# vl822.net
KiCad netlist of a schematic drawn in Altium Designer
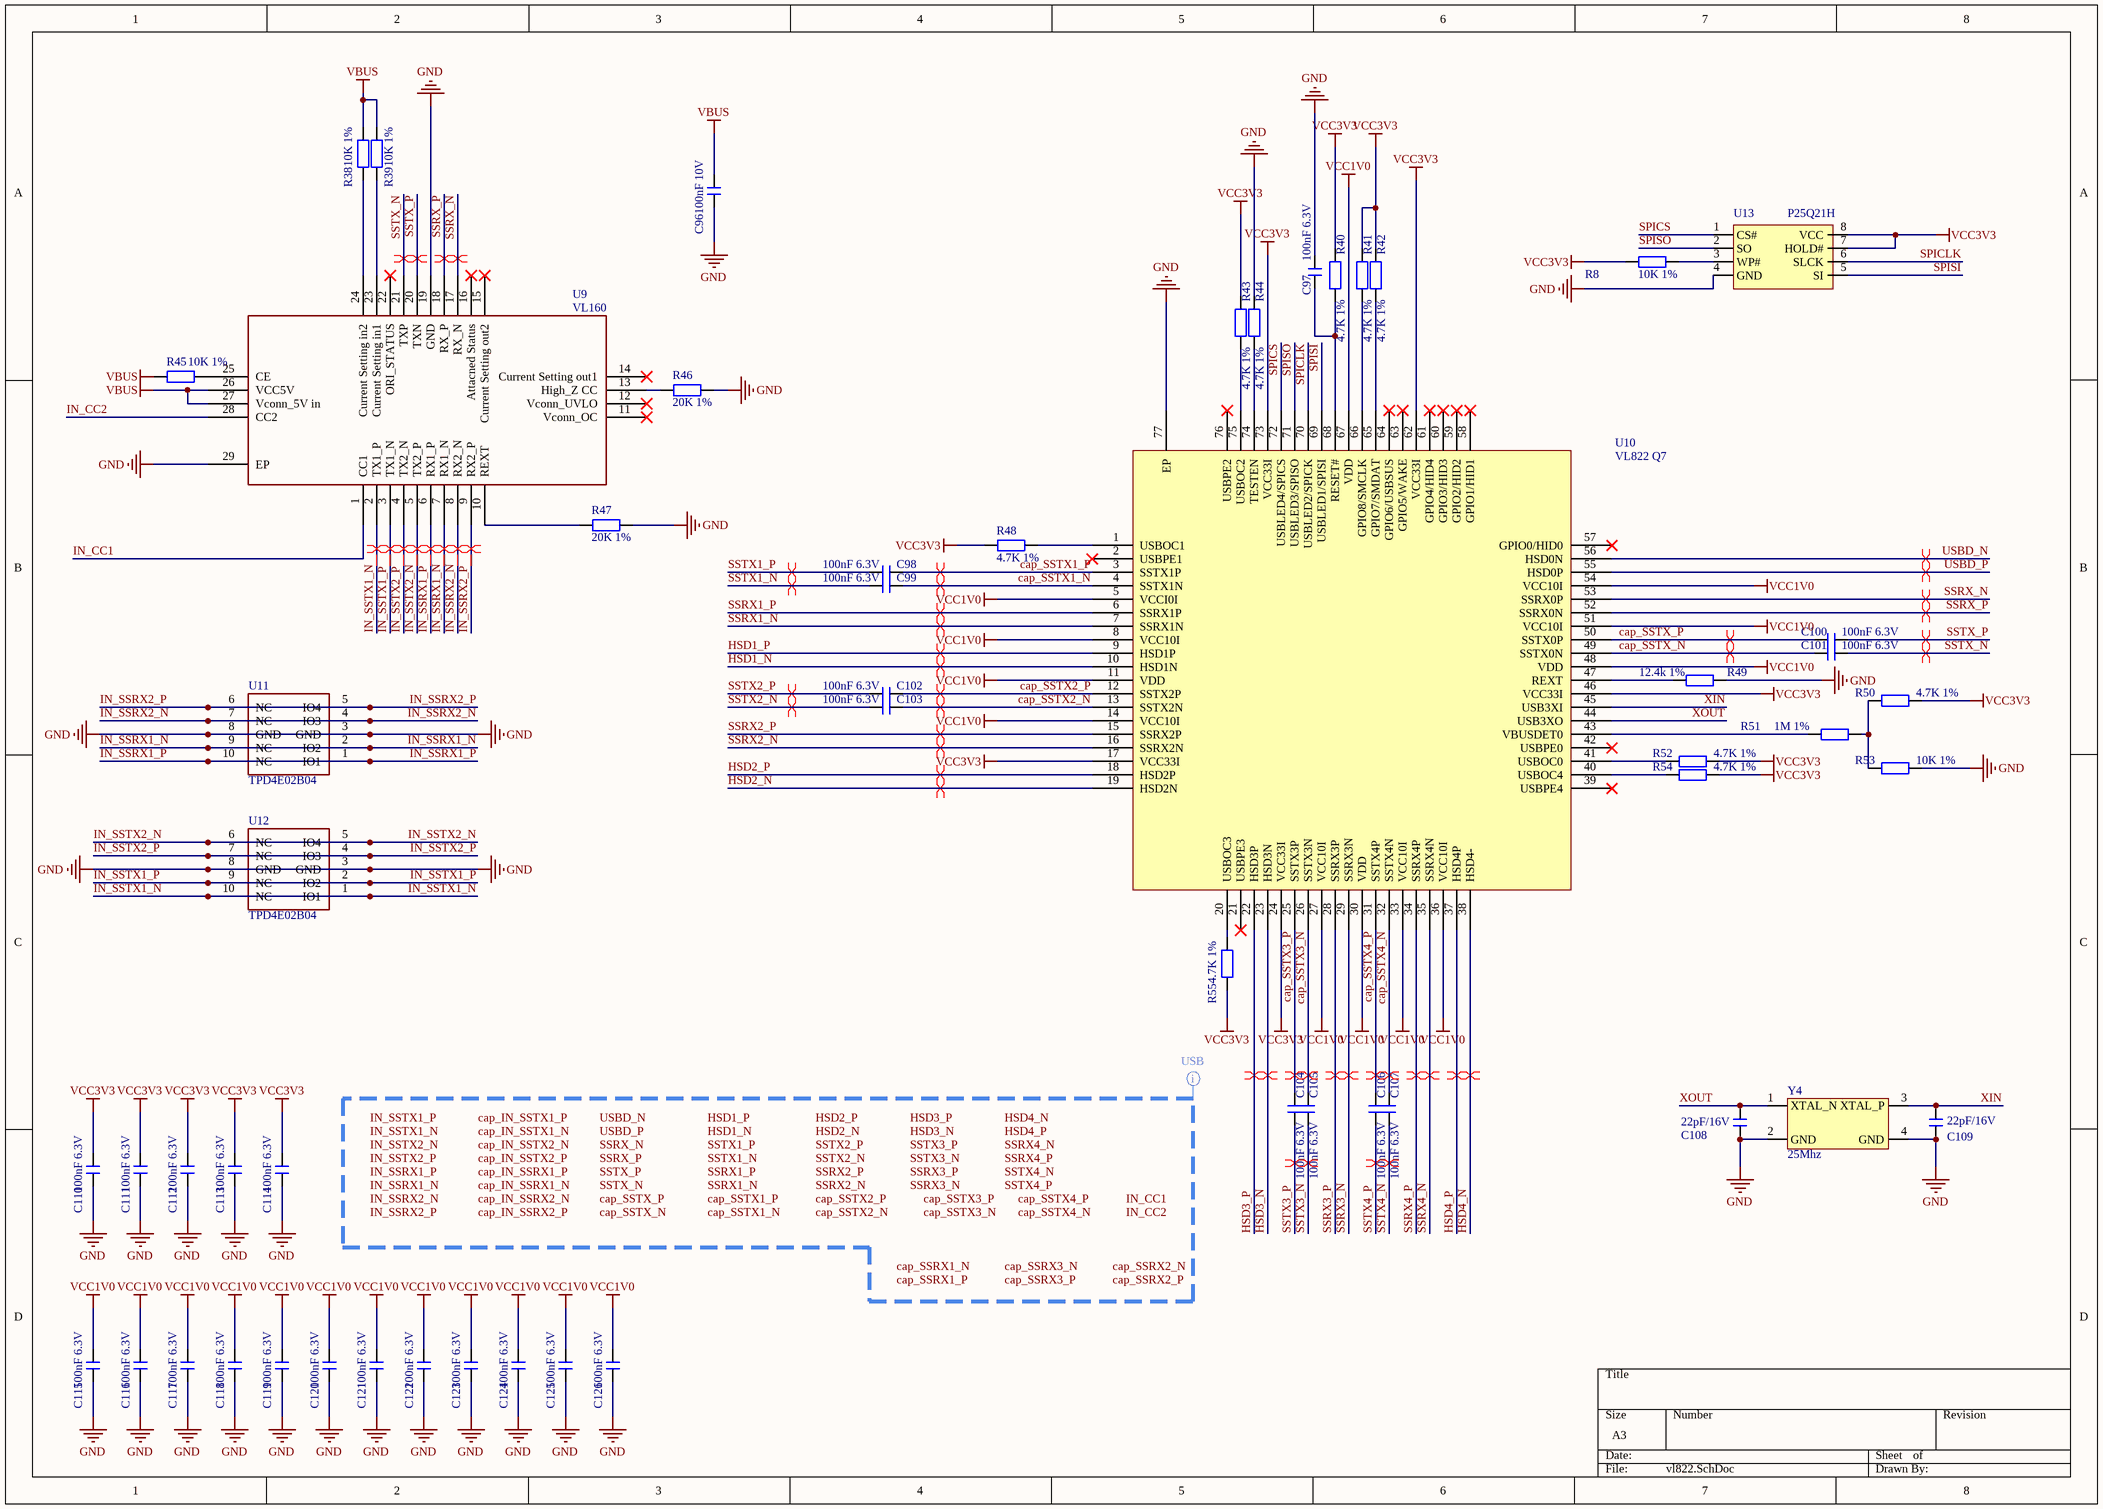
[diagram p0: vl822.SchDoc]

(export (version "E")
  (design (tool "Eeschema 10.0.6"))
  (components
    (comp (ref "C96")
      (value "100nF 10V")
      (footprint "C0402_L")
      (description "无极性贴片电容")
      (fields (field (name "版权归属") "源创客"))
      (libsource (lib "Capacitor") (part "C"))
    )
    (comp (ref "C97")
      (value "100nF 6.3V")
      (footprint "C0402_L")
      (description "无极性贴片电容")
      (fields (field (name "版权归属") "源创客"))
      (libsource (lib "Capacitor") (part "C"))
    )
    (comp (ref "C98")
      (value "100nF 6.3V")
      (footprint "C0402_L")
      (description "无极性贴片电容")
      (fields (field (name "版权归属") "源创客"))
      (libsource (lib "Capacitor") (part "C"))
    )
    (comp (ref "C99")
      (value "100nF 6.3V")
      (footprint "C0402_L")
      (description "无极性贴片电容")
      (fields (field (name "版权归属") "源创客"))
      (libsource (lib "Capacitor") (part "C"))
    )
    (comp (ref "C100")
      (value "100nF 6.3V")
      (footprint "C0402_L")
      (description "无极性贴片电容")
      (fields (field (name "版权归属") "源创客"))
      (libsource (lib "Capacitor") (part "C"))
    )
    (comp (ref "C101")
      (value "100nF 6.3V")
      (footprint "C0402_L")
      (description "无极性贴片电容")
      (fields (field (name "版权归属") "源创客"))
      (libsource (lib "Capacitor") (part "C"))
    )
    (comp (ref "C102")
      (value "100nF 6.3V")
      (footprint "C0402_L")
      (description "无极性贴片电容")
      (fields (field (name "版权归属") "源创客"))
      (libsource (lib "Capacitor") (part "C"))
    )
    (comp (ref "C103")
      (value "100nF 6.3V")
      (footprint "C0402_L")
      (description "无极性贴片电容")
      (fields (field (name "版权归属") "源创客"))
      (libsource (lib "Capacitor") (part "C"))
    )
    (comp (ref "C104")
      (value "100nF 6.3V")
      (footprint "C0402_L")
      (description "无极性贴片电容")
      (fields (field (name "版权归属") "源创客"))
      (libsource (lib "Capacitor") (part "C"))
    )
    (comp (ref "C105")
      (value "100nF 6.3V")
      (footprint "C0402_L")
      (description "无极性贴片电容")
      (fields (field (name "版权归属") "源创客"))
      (libsource (lib "Capacitor") (part "C"))
    )
    (comp (ref "C106")
      (value "100nF 6.3V")
      (footprint "C0402_L")
      (description "无极性贴片电容")
      (fields (field (name "版权归属") "源创客"))
      (libsource (lib "Capacitor") (part "C"))
    )
    (comp (ref "C107")
      (value "100nF 6.3V")
      (footprint "C0402_L")
      (description "无极性贴片电容")
      (fields (field (name "版权归属") "源创客"))
      (libsource (lib "Capacitor") (part "C"))
    )
    (comp (ref "C108")
      (value "22pF/16V")
      (footprint "C0402_L")
      (description "无极性贴片电容")
      (fields (field (name "版权归属") "源创客"))
      (libsource (lib "Capacitor") (part "C"))
    )
    (comp (ref "C109")
      (value "22pF/16V")
      (footprint "C0402_L")
      (description "无极性贴片电容")
      (fields (field (name "版权归属") "源创客"))
      (libsource (lib "Capacitor") (part "C"))
    )
    (comp (ref "C110")
      (value "100nF 6.3V")
      (footprint "C0402_L")
      (description "无极性贴片电容")
      (fields (field (name "版权归属") "源创客"))
      (libsource (lib "Capacitor") (part "C"))
    )
    (comp (ref "C111")
      (value "100nF 6.3V")
      (footprint "C0402_L")
      (description "无极性贴片电容")
      (fields (field (name "版权归属") "源创客"))
      (libsource (lib "Capacitor") (part "C"))
    )
    (comp (ref "C112")
      (value "100nF 6.3V")
      (footprint "C0402_L")
      (description "无极性贴片电容")
      (fields (field (name "版权归属") "源创客"))
      (libsource (lib "Capacitor") (part "C"))
    )
    (comp (ref "C113")
      (value "100nF 6.3V")
      (footprint "C0402_L")
      (description "无极性贴片电容")
      (fields (field (name "版权归属") "源创客"))
      (libsource (lib "Capacitor") (part "C"))
    )
    (comp (ref "C114")
      (value "100nF 6.3V")
      (footprint "C0402_L")
      (description "无极性贴片电容")
      (fields (field (name "版权归属") "源创客"))
      (libsource (lib "Capacitor") (part "C"))
    )
    (comp (ref "C115")
      (value "100nF 6.3V")
      (footprint "C0402_L")
      (description "无极性贴片电容")
      (fields (field (name "版权归属") "源创客"))
      (libsource (lib "Capacitor") (part "C"))
    )
    (comp (ref "C116")
      (value "100nF 6.3V")
      (footprint "C0402_L")
      (description "无极性贴片电容")
      (fields (field (name "版权归属") "源创客"))
      (libsource (lib "Capacitor") (part "C"))
    )
    (comp (ref "C117")
      (value "100nF 6.3V")
      (footprint "C0402_L")
      (description "无极性贴片电容")
      (fields (field (name "版权归属") "源创客"))
      (libsource (lib "Capacitor") (part "C"))
    )
    (comp (ref "C118")
      (value "100nF 6.3V")
      (footprint "C0402_L")
      (description "无极性贴片电容")
      (fields (field (name "版权归属") "源创客"))
      (libsource (lib "Capacitor") (part "C"))
    )
    (comp (ref "C119")
      (value "100nF 6.3V")
      (footprint "C0402_L")
      (description "无极性贴片电容")
      (fields (field (name "版权归属") "源创客"))
      (libsource (lib "Capacitor") (part "C"))
    )
    (comp (ref "C120")
      (value "100nF 6.3V")
      (footprint "C0402_L")
      (description "无极性贴片电容")
      (fields (field (name "版权归属") "源创客"))
      (libsource (lib "Capacitor") (part "C"))
    )
    (comp (ref "C121")
      (value "100nF 6.3V")
      (footprint "C0402_L")
      (description "无极性贴片电容")
      (fields (field (name "版权归属") "源创客"))
      (libsource (lib "Capacitor") (part "C"))
    )
    (comp (ref "C122")
      (value "100nF 6.3V")
      (footprint "C0402_L")
      (description "无极性贴片电容")
      (fields (field (name "版权归属") "源创客"))
      (libsource (lib "Capacitor") (part "C"))
    )
    (comp (ref "C123")
      (value "100nF 6.3V")
      (footprint "C0402_L")
      (description "无极性贴片电容")
      (fields (field (name "版权归属") "源创客"))
      (libsource (lib "Capacitor") (part "C"))
    )
    (comp (ref "C124")
      (value "100nF 6.3V")
      (footprint "C0402_L")
      (description "无极性贴片电容")
      (fields (field (name "版权归属") "源创客"))
      (libsource (lib "Capacitor") (part "C"))
    )
    (comp (ref "C125")
      (value "100nF 6.3V")
      (footprint "C0402_L")
      (description "无极性贴片电容")
      (fields (field (name "版权归属") "源创客"))
      (libsource (lib "Capacitor") (part "C"))
    )
    (comp (ref "C126")
      (value "100nF 6.3V")
      (footprint "C0402_L")
      (description "无极性贴片电容")
      (fields (field (name "版权归属") "源创客"))
      (libsource (lib "Capacitor") (part "C"))
    )
    (comp (ref "R8")
      (value "10K 1%")
      (footprint "R0402_L")
      (description "贴片电阻")
      (fields (field (name "版权归属") "源创客"))
      (libsource (lib "Resistor") (part "R"))
    )
    (comp (ref "R38")
      (value "10K 1%")
      (footprint "R0402_L")
      (description "贴片电阻")
      (fields (field (name "版权归属") "源创客"))
      (libsource (lib "Resistor") (part "R"))
    )
    (comp (ref "R39")
      (value "10K 1%")
      (footprint "R0402_L")
      (description "贴片电阻")
      (fields (field (name "版权归属") "源创客"))
      (libsource (lib "Resistor") (part "R"))
    )
    (comp (ref "R40")
      (value "4.7K 1%")
      (footprint "R0402_L")
      (description "贴片电阻")
      (fields (field (name "版权归属") "源创客"))
      (libsource (lib "Resistor") (part "R"))
    )
    (comp (ref "R41")
      (value "4.7K 1%")
      (footprint "R0402_L")
      (description "贴片电阻")
      (fields (field (name "版权归属") "源创客"))
      (libsource (lib "Resistor") (part "R"))
    )
    (comp (ref "R42")
      (value "4.7K 1%")
      (footprint "R0402_L")
      (description "贴片电阻")
      (fields (field (name "版权归属") "源创客"))
      (libsource (lib "Resistor") (part "R"))
    )
    (comp (ref "R43")
      (value "4.7K 1%")
      (footprint "R0402_L")
      (description "贴片电阻")
      (fields (field (name "版权归属") "源创客"))
      (libsource (lib "Resistor") (part "R"))
    )
    (comp (ref "R44")
      (value "4.7K 1%")
      (footprint "R0402_L")
      (description "贴片电阻")
      (fields (field (name "版权归属") "源创客"))
      (libsource (lib "Resistor") (part "R"))
    )
    (comp (ref "R45")
      (value "10K 1%")
      (footprint "R0402_L")
      (description "贴片电阻")
      (fields (field (name "版权归属") "源创客"))
      (libsource (lib "Resistor") (part "R"))
    )
    (comp (ref "R46")
      (value "20K 1%")
      (footprint "R0402_L")
      (description "贴片电阻")
      (fields (field (name "版权归属") "源创客"))
      (libsource (lib "Resistor") (part "R"))
    )
    (comp (ref "R47")
      (value "20K 1%")
      (footprint "R0402_L")
      (description "贴片电阻")
      (fields (field (name "版权归属") "源创客"))
      (libsource (lib "Resistor") (part "R"))
    )
    (comp (ref "R48")
      (value "4.7K 1%")
      (footprint "R0402_L")
      (description "贴片电阻")
      (fields (field (name "版权归属") "源创客"))
      (libsource (lib "Resistor") (part "R"))
    )
    (comp (ref "R49")
      (value "12.4k 1%")
      (footprint "R0402_L")
      (description "贴片电阻")
      (fields (field (name "版权归属") "源创客"))
      (libsource (lib "Resistor") (part "R"))
    )
    (comp (ref "R50")
      (value "4.7K 1%")
      (footprint "R0402_L")
      (description "贴片电阻")
      (fields (field (name "版权归属") "源创客"))
      (libsource (lib "Resistor") (part "R"))
    )
    (comp (ref "R51")
      (value "1M 1%")
      (footprint "R0402_L")
      (description "贴片电阻")
      (fields (field (name "版权归属") "源创客"))
      (libsource (lib "Resistor") (part "R"))
    )
    (comp (ref "R52")
      (value "4.7K 1%")
      (footprint "R0402_L")
      (description "贴片电阻")
      (fields (field (name "版权归属") "源创客"))
      (libsource (lib "Resistor") (part "R"))
    )
    (comp (ref "R53")
      (value "10K 1%")
      (footprint "R0402_L")
      (description "贴片电阻")
      (fields (field (name "版权归属") "源创客"))
      (libsource (lib "Resistor") (part "R"))
    )
    (comp (ref "R54")
      (value "4.7K 1%")
      (footprint "R0402_L")
      (description "贴片电阻")
      (fields (field (name "版权归属") "源创客"))
      (libsource (lib "Resistor") (part "R"))
    )
    (comp (ref "R55")
      (value "4.7K 1%")
      (footprint "R0402_L")
      (description "贴片电阻")
      (fields (field (name "版权归属") "源创客"))
      (libsource (lib "Resistor") (part "R"))
    )
    (comp (ref "U9")
      (value "VL160")
      (footprint "MQFN-28_L4.5-W3.5-P0.40-BL-EP")
      (libsource (lib "Brage") (part "VL160"))
    )
    (comp (ref "U10")
      (value "VL822 Q7")
      (footprint "QFN-76_L9.0-W9.0-P0.40-EP6.3-TL")
      (libsource (lib "Brage") (part "VL822 Q7"))
    )
    (comp (ref "U11")
      (value "TPD4E02B04")
      (footprint "DIO_TPD4E02B04DQAR")
      (description "ESD")
      (libsource (lib "Diode") (part "TPD4E02B04"))
    )
    (comp (ref "U12")
      (value "TPD4E02B04")
      (footprint "DIO_TPD4E02B04DQAR")
      (description "ESD")
      (libsource (lib "Diode") (part "TPD4E02B04"))
    )
    (comp (ref "U13") (value "P25Q21H") (footprint "SOP8_L") (libsource (lib "Flash") (part "P25D40H")))
    (comp (ref "Y4") (value "25Mhz") (footprint "OSC 3225-4P") (libsource (lib "Crystal") (part "Crystal")))
  )
  (nets
    (net (code "1") (name "/HSD1_N") (class "Default")
      (node (ref "U10") (pin "10") (pinfunction "HSD1N_10") (pintype "passive"))
    )
    (net (code "2") (name "/HSD1_P") (class "Default")
      (node (ref "U10") (pin "9") (pinfunction "HSD1P_9") (pintype "passive"))
    )
    (net (code "3") (name "/HSD2_N") (class "Default")
      (node (ref "U10") (pin "19") (pinfunction "HSD2N_19") (pintype "passive"))
    )
    (net (code "4") (name "/HSD2_P") (class "Default")
      (node (ref "U10") (pin "18") (pinfunction "HSD2P_18") (pintype "passive"))
    )
    (net (code "5") (name "/HSD3_N") (class "Default")
      (node (ref "U10") (pin "23") (pinfunction "HSD3N_23") (pintype "passive"))
    )
    (net (code "6") (name "/HSD3_P") (class "Default")
      (node (ref "U10") (pin "22") (pinfunction "HSD3P_22") (pintype "passive"))
    )
    (net (code "7") (name "/HSD4_N") (class "Default")
      (node (ref "U10") (pin "38") (pinfunction "HSD4-_38") (pintype "passive"))
    )
    (net (code "8") (name "/HSD4_P") (class "Default")
      (node (ref "U10") (pin "37") (pinfunction "HSD4P_37") (pintype "passive"))
    )
    (net (code "9") (name "/IN_CC1") (class "Default")
      (node (ref "U9") (pin "1") (pinfunction "CC1_1") (pintype "passive"))
    )
    (net (code "10") (name "/IN_CC2") (class "Default")
      (node (ref "U9") (pin "28") (pinfunction "CC2_28") (pintype "passive"))
    )
    (net (code "11") (name "/IN_SSRX1_N") (class "Default")
      (node (ref "U11") (pin "2") (pinfunction "IO2_2") (pintype "passive"))
      (node (ref "U11") (pin "9") (pinfunction "NC_9") (pintype "passive"))
      (node (ref "U9") (pin "7") (pinfunction "RX1_N_7") (pintype "passive"))
    )
    (net (code "12") (name "/IN_SSRX1_P") (class "Default")
      (node (ref "U11") (pin "1") (pinfunction "IO1_1") (pintype "passive"))
      (node (ref "U11") (pin "10") (pinfunction "NC_10") (pintype "passive"))
      (node (ref "U9") (pin "6") (pinfunction "RX1_P_6") (pintype "passive"))
    )
    (net (code "13") (name "/IN_SSRX2_N") (class "Default")
      (node (ref "U11") (pin "4") (pinfunction "IO3_4") (pintype "passive"))
      (node (ref "U11") (pin "7") (pinfunction "NC_7") (pintype "passive"))
      (node (ref "U9") (pin "8") (pinfunction "RX2_N_8") (pintype "passive"))
    )
    (net (code "14") (name "/IN_SSRX2_P") (class "Default")
      (node (ref "U11") (pin "5") (pinfunction "IO4_5") (pintype "passive"))
      (node (ref "U11") (pin "6") (pinfunction "NC_6") (pintype "passive"))
      (node (ref "U9") (pin "9") (pinfunction "RX2_P_9") (pintype "passive"))
    )
    (net (code "15") (name "/IN_SSTX1_N") (class "Default")
      (node (ref "U12") (pin "1") (pinfunction "IO1_1") (pintype "passive"))
      (node (ref "U12") (pin "10") (pinfunction "NC_10") (pintype "passive"))
      (node (ref "U9") (pin "2") (pinfunction "TX1_P_2") (pintype "passive"))
    )
    (net (code "16") (name "/IN_SSTX1_P") (class "Default")
      (node (ref "U12") (pin "2") (pinfunction "IO2_2") (pintype "passive"))
      (node (ref "U12") (pin "9") (pinfunction "NC_9") (pintype "passive"))
      (node (ref "U9") (pin "3") (pinfunction "TX1_N_3") (pintype "passive"))
    )
    (net (code "17") (name "/IN_SSTX2_N") (class "Default")
      (node (ref "U12") (pin "5") (pinfunction "IO4_5") (pintype "passive"))
      (node (ref "U12") (pin "6") (pinfunction "NC_6") (pintype "passive"))
      (node (ref "U9") (pin "5") (pinfunction "TX2_P_5") (pintype "passive"))
    )
    (net (code "18") (name "/IN_SSTX2_P") (class "Default")
      (node (ref "U12") (pin "4") (pinfunction "IO3_4") (pintype "passive"))
      (node (ref "U12") (pin "7") (pinfunction "NC_7") (pintype "passive"))
      (node (ref "U9") (pin "4") (pinfunction "TX2_N_4") (pintype "passive"))
    )
    (net (code "19") (name "/SPICLK") (class "Default")
      (node (ref "U10") (pin "70") (pinfunction "USBLED2/SPICK_70") (pintype "passive"))
      (node (ref "U13") (pin "6") (pinfunction "SLCK_6") (pintype "passive"))
    )
    (net (code "20") (name "/SPICS") (class "Default")
      (node (ref "U10") (pin "72") (pinfunction "USBLED4/SPICS_72") (pintype "passive"))
      (node (ref "U13") (pin "1") (pinfunction "CS#_1") (pintype "passive"))
    )
    (net (code "21") (name "/SPISI") (class "Default")
      (node (ref "U10") (pin "69") (pinfunction "USBLED1/SPISI_69") (pintype "passive"))
      (node (ref "U13") (pin "5") (pinfunction "SI_5") (pintype "passive"))
    )
    (net (code "22") (name "/SPISO") (class "Default")
      (node (ref "U10") (pin "71") (pinfunction "USBLED3/SPISO_71") (pintype "passive"))
      (node (ref "U13") (pin "2") (pinfunction "SO_2") (pintype "passive"))
    )
    (net (code "23") (name "/SSRX1_N") (class "Default")
      (node (ref "U10") (pin "7") (pinfunction "SSRX1N_7") (pintype "passive"))
    )
    (net (code "24") (name "/SSRX1_P") (class "Default")
      (node (ref "U10") (pin "6") (pinfunction "SSRX1P_6") (pintype "passive"))
    )
    (net (code "25") (name "/SSRX2_N") (class "Default")
      (node (ref "U10") (pin "16") (pinfunction "SSRX2N_16") (pintype "passive"))
    )
    (net (code "26") (name "/SSRX2_P") (class "Default")
      (node (ref "U10") (pin "15") (pinfunction "SSRX2P_15") (pintype "passive"))
    )
    (net (code "27") (name "/SSRX3_N") (class "Default")
      (node (ref "U10") (pin "29") (pinfunction "SSRX3N_29") (pintype "passive"))
    )
    (net (code "28") (name "/SSRX3_P") (class "Default")
      (node (ref "U10") (pin "28") (pinfunction "SSRX3P_28") (pintype "passive"))
    )
    (net (code "29") (name "/SSRX4_N") (class "Default")
      (node (ref "U10") (pin "35") (pinfunction "SSRX4N_35") (pintype "passive"))
    )
    (net (code "30") (name "/SSRX4_P") (class "Default")
      (node (ref "U10") (pin "34") (pinfunction "SSRX4P_34") (pintype "passive"))
    )
    (net (code "31") (name "/SSRX_N") (class "Default")
      (node (ref "U10") (pin "53") (pinfunction "SSRX0P_53") (pintype "passive"))
      (node (ref "U9") (pin "17") (pinfunction "RX_N_17") (pintype "passive"))
    )
    (net (code "32") (name "/SSRX_P") (class "Default")
      (node (ref "U10") (pin "52") (pinfunction "SSRX0N_52") (pintype "passive"))
      (node (ref "U9") (pin "18") (pinfunction "RX_P_18") (pintype "passive"))
    )
    (net (code "33") (name "/SSTX1_N") (class "Default")
      (node (ref "C99") (pin "1") (pinfunction "1_1") (pintype "passive"))
    )
    (net (code "34") (name "/SSTX1_P") (class "Default")
      (node (ref "C98") (pin "1") (pinfunction "1_1") (pintype "passive"))
    )
    (net (code "35") (name "/SSTX2_N") (class "Default")
      (node (ref "C103") (pin "1") (pinfunction "1_1") (pintype "passive"))
    )
    (net (code "36") (name "/SSTX2_P") (class "Default")
      (node (ref "C102") (pin "1") (pinfunction "1_1") (pintype "passive"))
    )
    (net (code "37") (name "/SSTX3_N") (class "Default")
      (node (ref "C105") (pin "1") (pinfunction "1_1") (pintype "passive"))
    )
    (net (code "38") (name "/SSTX3_P") (class "Default")
      (node (ref "C104") (pin "1") (pinfunction "1_1") (pintype "passive"))
    )
    (net (code "39") (name "/SSTX4_N") (class "Default")
      (node (ref "C107") (pin "1") (pinfunction "1_1") (pintype "passive"))
    )
    (net (code "40") (name "/SSTX4_P") (class "Default")
      (node (ref "C106") (pin "1") (pinfunction "1_1") (pintype "passive"))
    )
    (net (code "41") (name "/SSTX_N") (class "Default")
      (node (ref "C101") (pin "1") (pinfunction "1_1") (pintype "passive"))
      (node (ref "U9") (pin "21") (pinfunction "TXP_21") (pintype "passive"))
    )
    (net (code "42") (name "/SSTX_P") (class "Default")
      (node (ref "C100") (pin "1") (pinfunction "1_1") (pintype "passive"))
      (node (ref "U9") (pin "20") (pinfunction "TXN_20") (pintype "passive"))
    )
    (net (code "43") (name "/USBD_N") (class "Default")
      (node (ref "U10") (pin "56") (pinfunction "HSD0N_56") (pintype "passive"))
    )
    (net (code "44") (name "/USBD_P") (class "Default")
      (node (ref "U10") (pin "55") (pinfunction "HSD0P_55") (pintype "passive"))
    )
    (net (code "45") (name "/XIN") (class "Default")
      (node (ref "C109") (pin "1") (pinfunction "1_1") (pintype "passive"))
      (node (ref "U10") (pin "45") (pinfunction "USB3XI_45") (pintype "passive"))
      (node (ref "Y4") (pin "3") (pinfunction "XTAL_P_3") (pintype "passive"))
    )
    (net (code "46") (name "/XOUT") (class "Default")
      (node (ref "C108") (pin "1") (pinfunction "1_1") (pintype "passive"))
      (node (ref "U10") (pin "44") (pinfunction "USB3XO_44") (pintype "passive"))
      (node (ref "Y4") (pin "1") (pinfunction "XTAL_N_1") (pintype "passive"))
    )
    (net (code "61") (name "/cap_SSTX1_N") (class "Default")
      (node (ref "C99") (pin "2") (pinfunction "2_2") (pintype "passive"))
      (node (ref "U10") (pin "4") (pinfunction "SSTX1N_4") (pintype "passive"))
    )
    (net (code "62") (name "/cap_SSTX1_P") (class "Default")
      (node (ref "C98") (pin "2") (pinfunction "2_2") (pintype "passive"))
      (node (ref "U10") (pin "3") (pinfunction "SSTX1P_3") (pintype "passive"))
    )
    (net (code "63") (name "/cap_SSTX2_N") (class "Default")
      (node (ref "C103") (pin "2") (pinfunction "2_2") (pintype "passive"))
      (node (ref "U10") (pin "13") (pinfunction "SSTX2N_13") (pintype "passive"))
    )
    (net (code "64") (name "/cap_SSTX2_P") (class "Default")
      (node (ref "C102") (pin "2") (pinfunction "2_2") (pintype "passive"))
      (node (ref "U10") (pin "12") (pinfunction "SSTX2P_12") (pintype "passive"))
    )
    (net (code "65") (name "/cap_SSTX3_N") (class "Default")
      (node (ref "C105") (pin "2") (pinfunction "2_2") (pintype "passive"))
      (node (ref "U10") (pin "26") (pinfunction "SSTX3N_26") (pintype "passive"))
    )
    (net (code "66") (name "/cap_SSTX3_P") (class "Default")
      (node (ref "C104") (pin "2") (pinfunction "2_2") (pintype "passive"))
      (node (ref "U10") (pin "25") (pinfunction "SSTX3P_25") (pintype "passive"))
    )
    (net (code "67") (name "/cap_SSTX4_N") (class "Default")
      (node (ref "C107") (pin "2") (pinfunction "2_2") (pintype "passive"))
      (node (ref "U10") (pin "32") (pinfunction "SSTX4N_32") (pintype "passive"))
    )
    (net (code "68") (name "/cap_SSTX4_P") (class "Default")
      (node (ref "C106") (pin "2") (pinfunction "2_2") (pintype "passive"))
      (node (ref "U10") (pin "31") (pinfunction "SSTX4P_31") (pintype "passive"))
    )
    (net (code "69") (name "/cap_SSTX_N") (class "Default")
      (node (ref "C101") (pin "2") (pinfunction "2_2") (pintype "passive"))
      (node (ref "U10") (pin "49") (pinfunction "SSTX0N_49") (pintype "passive"))
    )
    (net (code "70") (name "/cap_SSTX_P") (class "Default")
      (node (ref "C100") (pin "2") (pinfunction "2_2") (pintype "passive"))
      (node (ref "U10") (pin "50") (pinfunction "SSTX0P_50") (pintype "passive"))
    )
    (net (code "71") (name "GND") (class "Default")
      (node (ref "C108") (pin "2") (pinfunction "2_2") (pintype "passive"))
      (node (ref "C109") (pin "2") (pinfunction "2_2") (pintype "passive"))
      (node (ref "C110") (pin "1") (pinfunction "1_1") (pintype "passive"))
      (node (ref "C111") (pin "1") (pinfunction "1_1") (pintype "passive"))
      (node (ref "C112") (pin "1") (pinfunction "1_1") (pintype "passive"))
      (node (ref "C113") (pin "1") (pinfunction "1_1") (pintype "passive"))
      (node (ref "C114") (pin "1") (pinfunction "1_1") (pintype "passive"))
      (node (ref "C115") (pin "1") (pinfunction "1_1") (pintype "passive"))
      (node (ref "C116") (pin "1") (pinfunction "1_1") (pintype "passive"))
      (node (ref "C117") (pin "1") (pinfunction "1_1") (pintype "passive"))
      (node (ref "C118") (pin "1") (pinfunction "1_1") (pintype "passive"))
      (node (ref "C119") (pin "1") (pinfunction "1_1") (pintype "passive"))
      (node (ref "C120") (pin "1") (pinfunction "1_1") (pintype "passive"))
      (node (ref "C121") (pin "1") (pinfunction "1_1") (pintype "passive"))
      (node (ref "C122") (pin "1") (pinfunction "1_1") (pintype "passive"))
      (node (ref "C123") (pin "1") (pinfunction "1_1") (pintype "passive"))
      (node (ref "C124") (pin "1") (pinfunction "1_1") (pintype "passive"))
      (node (ref "C125") (pin "1") (pinfunction "1_1") (pintype "passive"))
      (node (ref "C126") (pin "1") (pinfunction "1_1") (pintype "passive"))
      (node (ref "C96") (pin "1") (pinfunction "1_1") (pintype "passive"))
      (node (ref "C97") (pin "2") (pinfunction "2_2") (pintype "passive"))
      (node (ref "R44") (pin "2") (pinfunction "2_2") (pintype "passive"))
      (node (ref "R46") (pin "1") (pinfunction "1_1") (pintype "passive"))
      (node (ref "R47") (pin "1") (pinfunction "1_1") (pintype "passive"))
      (node (ref "R49") (pin "2") (pinfunction "2_2") (pintype "passive"))
      (node (ref "R53") (pin "2") (pinfunction "2_2") (pintype "passive"))
      (node (ref "U10") (pin "77") (pinfunction "EP_77") (pintype "passive"))
      (node (ref "U11") (pin "3") (pinfunction "GND_3") (pintype "passive"))
      (node (ref "U11") (pin "8") (pinfunction "GND_8") (pintype "passive"))
      (node (ref "U12") (pin "3") (pinfunction "GND_3") (pintype "passive"))
      (node (ref "U12") (pin "8") (pinfunction "GND_8") (pintype "passive"))
      (node (ref "U13") (pin "4") (pinfunction "GND_4") (pintype "passive"))
      (node (ref "U9") (pin "19") (pinfunction "GND_19") (pintype "passive"))
      (node (ref "U9") (pin "29") (pinfunction "EP_29") (pintype "passive"))
      (node (ref "Y4") (pin "2") (pinfunction "GND_2") (pintype "passive"))
      (node (ref "Y4") (pin "4") (pinfunction "GND_4") (pintype "passive"))
    )
    (net (code "72") (name "Net-(R50-Pad1)") (class "Default")
      (node (ref "R50") (pin "1") (pinfunction "1_1") (pintype "passive"))
      (node (ref "R51") (pin "2") (pinfunction "2_2") (pintype "passive"))
      (node (ref "R53") (pin "1") (pinfunction "1_1") (pintype "passive"))
    )
    (net (code "73") (name "Net-(U9-CE)") (class "Default")
      (node (ref "R45") (pin "1") (pinfunction "1_1") (pintype "passive"))
      (node (ref "U9") (pin "25") (pinfunction "CE_25") (pintype "passive"))
    )
    (net (code "74") (name "Net-(U9-Current_Setting_in1)") (class "Default")
      (node (ref "R39") (pin "2") (pinfunction "2_2") (pintype "passive"))
      (node (ref "U9") (pin "23") (pinfunction "Current_Setting_in1_23") (pintype "passive"))
    )
    (net (code "75") (name "Net-(U9-Current_Setting_in2)") (class "Default")
      (node (ref "R38") (pin "2") (pinfunction "2_2") (pintype "passive"))
      (node (ref "U9") (pin "24") (pinfunction "Current_Setting_in2_24") (pintype "passive"))
    )
    (net (code "76") (name "Net-(U9-High_Z_CC)") (class "Default")
      (node (ref "R46") (pin "2") (pinfunction "2_2") (pintype "passive"))
      (node (ref "U9") (pin "13") (pinfunction "High_Z_CC_13") (pintype "passive"))
    )
    (net (code "77") (name "Net-(U9-REXT)") (class "Default")
      (node (ref "R47") (pin "2") (pinfunction "2_2") (pintype "passive"))
      (node (ref "U9") (pin "10") (pinfunction "REXT_10") (pintype "passive"))
    )
    (net (code "78") (name "Net-(U10-GPIO7{slash}SMDAT)") (class "Default")
      (node (ref "R42") (pin "1") (pinfunction "1_1") (pintype "passive"))
      (node (ref "U10") (pin "65") (pinfunction "GPIO7/SMDAT_65") (pintype "passive"))
    )
    (net (code "79") (name "Net-(U10-GPIO8{slash}SMCLK)") (class "Default")
      (node (ref "R41") (pin "1") (pinfunction "1_1") (pintype "passive"))
      (node (ref "U10") (pin "66") (pinfunction "GPIO8/SMCLK_66") (pintype "passive"))
    )
    (net (code "80") (name "Net-(U10-RESET#)") (class "Default")
      (node (ref "C97") (pin "1") (pinfunction "1_1") (pintype "passive"))
      (node (ref "R40") (pin "1") (pinfunction "1_1") (pintype "passive"))
      (node (ref "U10") (pin "68") (pinfunction "RESET#_68") (pintype "passive"))
    )
    (net (code "81") (name "Net-(U10-REXT)") (class "Default")
      (node (ref "R49") (pin "1") (pinfunction "1_1") (pintype "passive"))
      (node (ref "U10") (pin "47") (pinfunction "REXT_47") (pintype "passive"))
    )
    (net (code "82") (name "Net-(U10-TESTEN)") (class "Default")
      (node (ref "R44") (pin "1") (pinfunction "1_1") (pintype "passive"))
      (node (ref "U10") (pin "74") (pinfunction "TESTEN_74") (pintype "passive"))
    )
    (net (code "83") (name "Net-(U10-USBOC0)") (class "Default")
      (node (ref "R52") (pin "1") (pinfunction "1_1") (pintype "passive"))
      (node (ref "U10") (pin "41") (pinfunction "USBOC0_41") (pintype "passive"))
    )
    (net (code "84") (name "Net-(U10-USBOC1)") (class "Default")
      (node (ref "R48") (pin "1") (pinfunction "1_1") (pintype "passive"))
      (node (ref "U10") (pin "1") (pinfunction "USBOC1_1") (pintype "passive"))
    )
    (net (code "85") (name "Net-(U10-USBOC2)") (class "Default")
      (node (ref "R43") (pin "1") (pinfunction "1_1") (pintype "passive"))
      (node (ref "U10") (pin "75") (pinfunction "USBOC2_75") (pintype "passive"))
    )
    (net (code "86") (name "Net-(U10-USBOC3)") (class "Default")
      (node (ref "R55") (pin "1") (pinfunction "1_1") (pintype "passive"))
      (node (ref "U10") (pin "20") (pinfunction "USBOC3_20") (pintype "passive"))
    )
    (net (code "87") (name "Net-(U10-USBOC4)") (class "Default")
      (node (ref "R54") (pin "1") (pinfunction "1_1") (pintype "passive"))
      (node (ref "U10") (pin "40") (pinfunction "USBOC4_40") (pintype "passive"))
    )
    (net (code "88") (name "Net-(U10-VBUSDET0)") (class "Default")
      (node (ref "R51") (pin "1") (pinfunction "1_1") (pintype "passive"))
      (node (ref "U10") (pin "43") (pinfunction "VBUSDET0_43") (pintype "passive"))
    )
    (net (code "89") (name "Net-(U13-WP#)") (class "Default")
      (node (ref "R8") (pin "1") (pinfunction "1_1") (pintype "passive"))
      (node (ref "U13") (pin "3") (pinfunction "WP#_3") (pintype "passive"))
    )
    (net (code "90") (name "VBUS") (class "Default")
      (node (ref "C96") (pin "2") (pinfunction "2_2") (pintype "passive"))
      (node (ref "R38") (pin "1") (pinfunction "1_1") (pintype "passive"))
      (node (ref "R39") (pin "1") (pinfunction "1_1") (pintype "passive"))
      (node (ref "R45") (pin "2") (pinfunction "2_2") (pintype "passive"))
      (node (ref "U9") (pin "26") (pinfunction "VCC5V_26") (pintype "passive"))
      (node (ref "U9") (pin "27") (pinfunction "Vconn_5V_in_27") (pintype "passive"))
    )
    (net (code "91") (name "VCC1V0") (class "Default")
      (node (ref "C115") (pin "2") (pinfunction "2_2") (pintype "passive"))
      (node (ref "C116") (pin "2") (pinfunction "2_2") (pintype "passive"))
      (node (ref "C117") (pin "2") (pinfunction "2_2") (pintype "passive"))
      (node (ref "C118") (pin "2") (pinfunction "2_2") (pintype "passive"))
      (node (ref "C119") (pin "2") (pinfunction "2_2") (pintype "passive"))
      (node (ref "C120") (pin "2") (pinfunction "2_2") (pintype "passive"))
      (node (ref "C121") (pin "2") (pinfunction "2_2") (pintype "passive"))
      (node (ref "C122") (pin "2") (pinfunction "2_2") (pintype "passive"))
      (node (ref "C123") (pin "2") (pinfunction "2_2") (pintype "passive"))
      (node (ref "C124") (pin "2") (pinfunction "2_2") (pintype "passive"))
      (node (ref "C125") (pin "2") (pinfunction "2_2") (pintype "passive"))
      (node (ref "C126") (pin "2") (pinfunction "2_2") (pintype "passive"))
      (node (ref "U10") (pin "11") (pinfunction "VDD_11") (pintype "passive"))
      (node (ref "U10") (pin "14") (pinfunction "VCC10I_14") (pintype "passive"))
      (node (ref "U10") (pin "27") (pinfunction "VCC10I_27") (pintype "passive"))
      (node (ref "U10") (pin "30") (pinfunction "VDD_30") (pintype "passive"))
      (node (ref "U10") (pin "33") (pinfunction "VCC10I_33") (pintype "passive"))
      (node (ref "U10") (pin "36") (pinfunction "VCC10I_36") (pintype "passive"))
      (node (ref "U10") (pin "48") (pinfunction "VDD_48") (pintype "passive"))
      (node (ref "U10") (pin "5") (pinfunction "VCCI0I_5") (pintype "passive"))
      (node (ref "U10") (pin "51") (pinfunction "VCC10I_51") (pintype "passive"))
      (node (ref "U10") (pin "54") (pinfunction "VCC10I_54") (pintype "passive"))
      (node (ref "U10") (pin "67") (pinfunction "VDD_67") (pintype "passive"))
      (node (ref "U10") (pin "8") (pinfunction "VCC10I_8") (pintype "passive"))
    )
    (net (code "92") (name "VCC3V3") (class "Default")
      (node (ref "C110") (pin "2") (pinfunction "2_2") (pintype "passive"))
      (node (ref "C111") (pin "2") (pinfunction "2_2") (pintype "passive"))
      (node (ref "C112") (pin "2") (pinfunction "2_2") (pintype "passive"))
      (node (ref "C113") (pin "2") (pinfunction "2_2") (pintype "passive"))
      (node (ref "C114") (pin "2") (pinfunction "2_2") (pintype "passive"))
      (node (ref "R40") (pin "2") (pinfunction "2_2") (pintype "passive"))
      (node (ref "R41") (pin "2") (pinfunction "2_2") (pintype "passive"))
      (node (ref "R42") (pin "2") (pinfunction "2_2") (pintype "passive"))
      (node (ref "R43") (pin "2") (pinfunction "2_2") (pintype "passive"))
      (node (ref "R48") (pin "2") (pinfunction "2_2") (pintype "passive"))
      (node (ref "R50") (pin "2") (pinfunction "2_2") (pintype "passive"))
      (node (ref "R52") (pin "2") (pinfunction "2_2") (pintype "passive"))
      (node (ref "R54") (pin "2") (pinfunction "2_2") (pintype "passive"))
      (node (ref "R55") (pin "2") (pinfunction "2_2") (pintype "passive"))
      (node (ref "R8") (pin "2") (pinfunction "2_2") (pintype "passive"))
      (node (ref "U10") (pin "17") (pinfunction "VCC33I_17") (pintype "passive"))
      (node (ref "U10") (pin "24") (pinfunction "VCC33I_24") (pintype "passive"))
      (node (ref "U10") (pin "46") (pinfunction "VCC33I_46") (pintype "passive"))
      (node (ref "U10") (pin "62") (pinfunction "VCC33I_62") (pintype "passive"))
      (node (ref "U10") (pin "73") (pinfunction "VCC33I_73") (pintype "passive"))
      (node (ref "U13") (pin "7") (pinfunction "HOLD#_7") (pintype "passive"))
      (node (ref "U13") (pin "8") (pinfunction "VCC_8") (pintype "passive"))
    )
    (net (code "93") (name "unconnected-(U9-Attacned_Status-Pad16)") (class "Default")
      (node (ref "U9") (pin "16") (pinfunction "Attacned_Status_16") (pintype "passive+no_connect"))
    )
    (net (code "94") (name "unconnected-(U9-Current_Setting_out1-Pad14)") (class "Default")
      (node (ref "U9") (pin "14") (pinfunction "Current_Setting_out1_14") (pintype "passive+no_connect"))
    )
    (net (code "95") (name "unconnected-(U9-Current_Setting_out2-Pad15)") (class "Default")
      (node (ref "U9") (pin "15") (pinfunction "Current_Setting_out2_15") (pintype "passive+no_connect"))
    )
    (net (code "96") (name "unconnected-(U9-ORI_STATUS-Pad22)") (class "Default")
      (node (ref "U9") (pin "22") (pinfunction "ORI_STATUS_22") (pintype "passive+no_connect"))
    )
    (net (code "97") (name "unconnected-(U9-Vconn_OC-Pad11)") (class "Default")
      (node (ref "U9") (pin "11") (pinfunction "Vconn_OC_11") (pintype "passive+no_connect"))
    )
    (net (code "98") (name "unconnected-(U9-Vconn_UVLO-Pad12)") (class "Default")
      (node (ref "U9") (pin "12") (pinfunction "Vconn_UVLO_12") (pintype "passive+no_connect"))
    )
    (net (code "99") (name "unconnected-(U10-GPIO0{slash}HID0-Pad57)") (class "Default")
      (node (ref "U10") (pin "57") (pinfunction "GPIO0/HID0_57") (pintype "passive+no_connect"))
    )
    (net (code "100") (name "unconnected-(U10-GPIO1{slash}HID1-Pad58)") (class "Default")
      (node (ref "U10") (pin "58") (pinfunction "GPIO1/HID1_58") (pintype "passive+no_connect"))
    )
    (net (code "101") (name "unconnected-(U10-GPIO2{slash}HID2-Pad59)") (class "Default")
      (node (ref "U10") (pin "59") (pinfunction "GPIO2/HID2_59") (pintype "passive+no_connect"))
    )
    (net (code "102") (name "unconnected-(U10-GPIO3{slash}HID3-Pad60)") (class "Default")
      (node (ref "U10") (pin "60") (pinfunction "GPIO3/HID3_60") (pintype "passive+no_connect"))
    )
    (net (code "103") (name "unconnected-(U10-GPIO4{slash}HID4-Pad61)") (class "Default")
      (node (ref "U10") (pin "61") (pinfunction "GPIO4/HID4_61") (pintype "passive+no_connect"))
    )
    (net (code "104") (name "unconnected-(U10-GPIO5{slash}WAKE-Pad63)") (class "Default")
      (node (ref "U10") (pin "63") (pinfunction "GPIO5/WAKE_63") (pintype "passive+no_connect"))
    )
    (net (code "105") (name "unconnected-(U10-GPIO6{slash}USBSUS-Pad64)") (class "Default")
      (node (ref "U10") (pin "64") (pinfunction "GPIO6/USBSUS_64") (pintype "passive+no_connect"))
    )
    (net (code "106") (name "unconnected-(U10-USBPE0-Pad42)") (class "Default")
      (node (ref "U10") (pin "42") (pinfunction "USBPE0_42") (pintype "passive+no_connect"))
    )
    (net (code "107") (name "unconnected-(U10-USBPE1-Pad2)") (class "Default")
      (node (ref "U10") (pin "2") (pinfunction "USBPE1_2") (pintype "passive+no_connect"))
    )
    (net (code "108") (name "unconnected-(U10-USBPE2-Pad76)") (class "Default")
      (node (ref "U10") (pin "76") (pinfunction "USBPE2_76") (pintype "passive+no_connect"))
    )
    (net (code "109") (name "unconnected-(U10-USBPE3-Pad21)") (class "Default")
      (node (ref "U10") (pin "21") (pinfunction "USBPE3_21") (pintype "passive+no_connect"))
    )
    (net (code "110") (name "unconnected-(U10-USBPE4-Pad39)") (class "Default")
      (node (ref "U10") (pin "39") (pinfunction "USBPE4_39") (pintype "passive+no_connect"))
    )
  )
)
